# revA-voltlog-mod.net
KiCad netlist of a schematic drawn in EAGLE
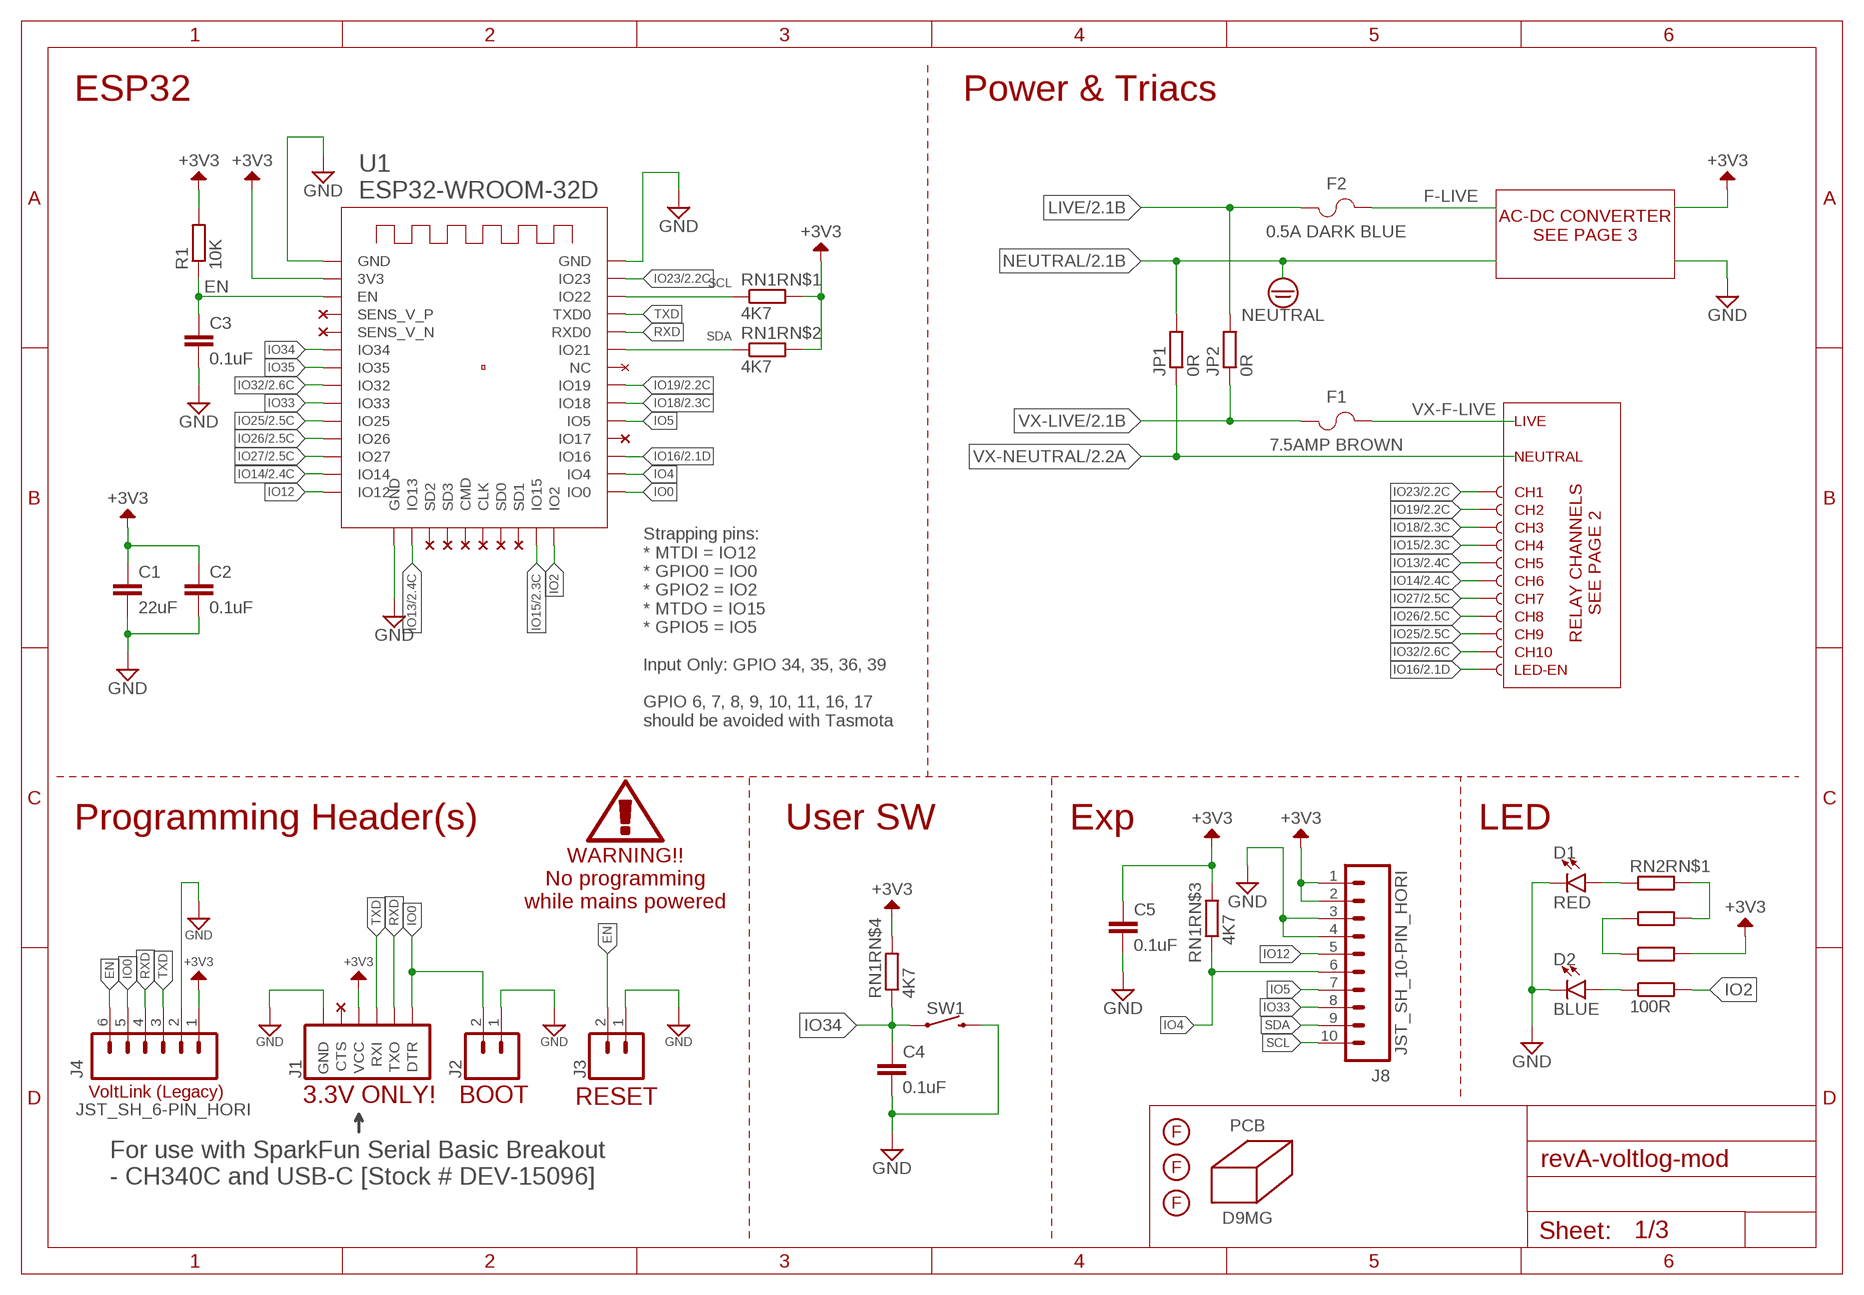
[diagram p0: schematic, sheet 1]
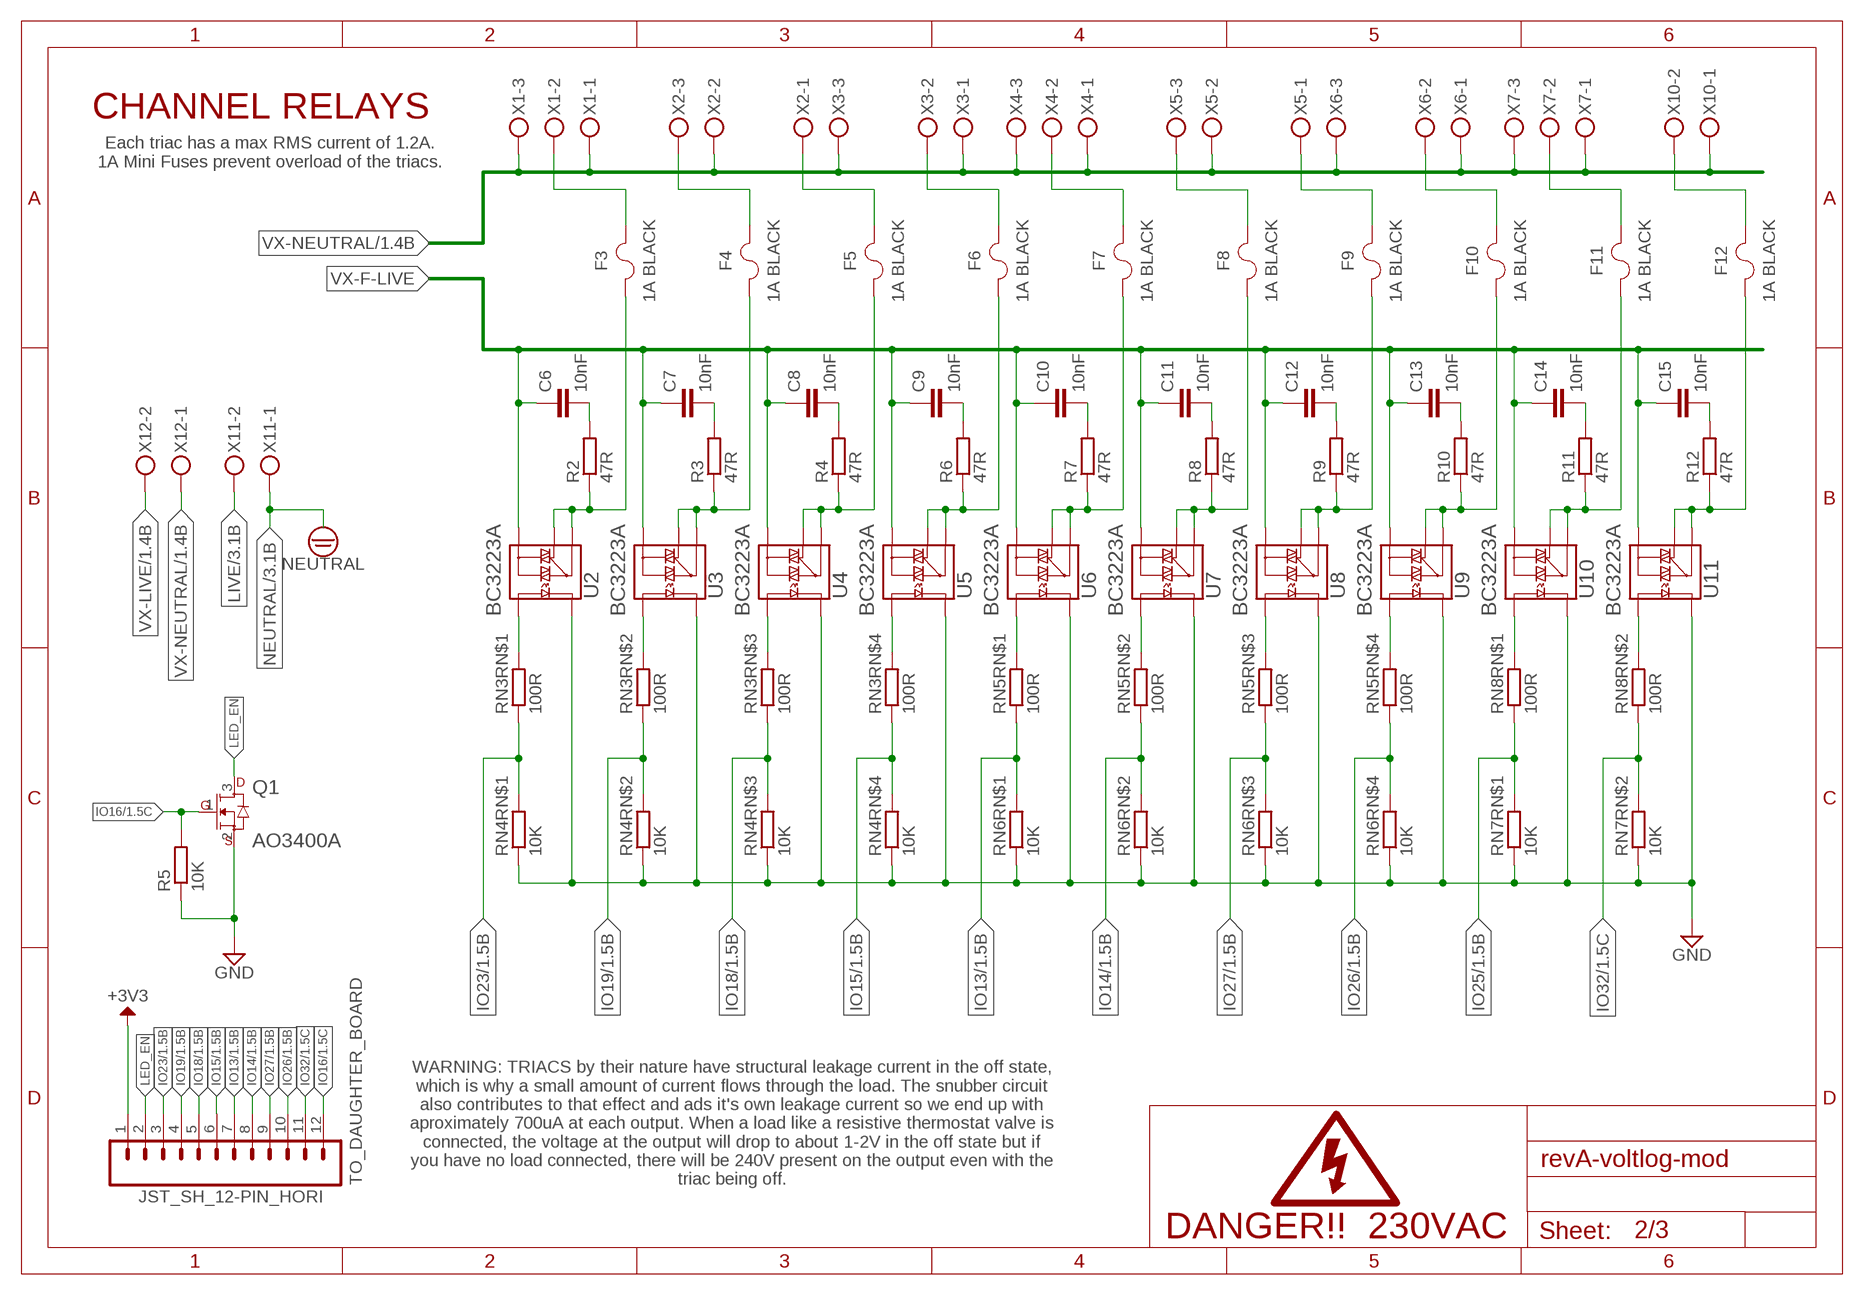
[diagram p1: schematic, sheet 2]
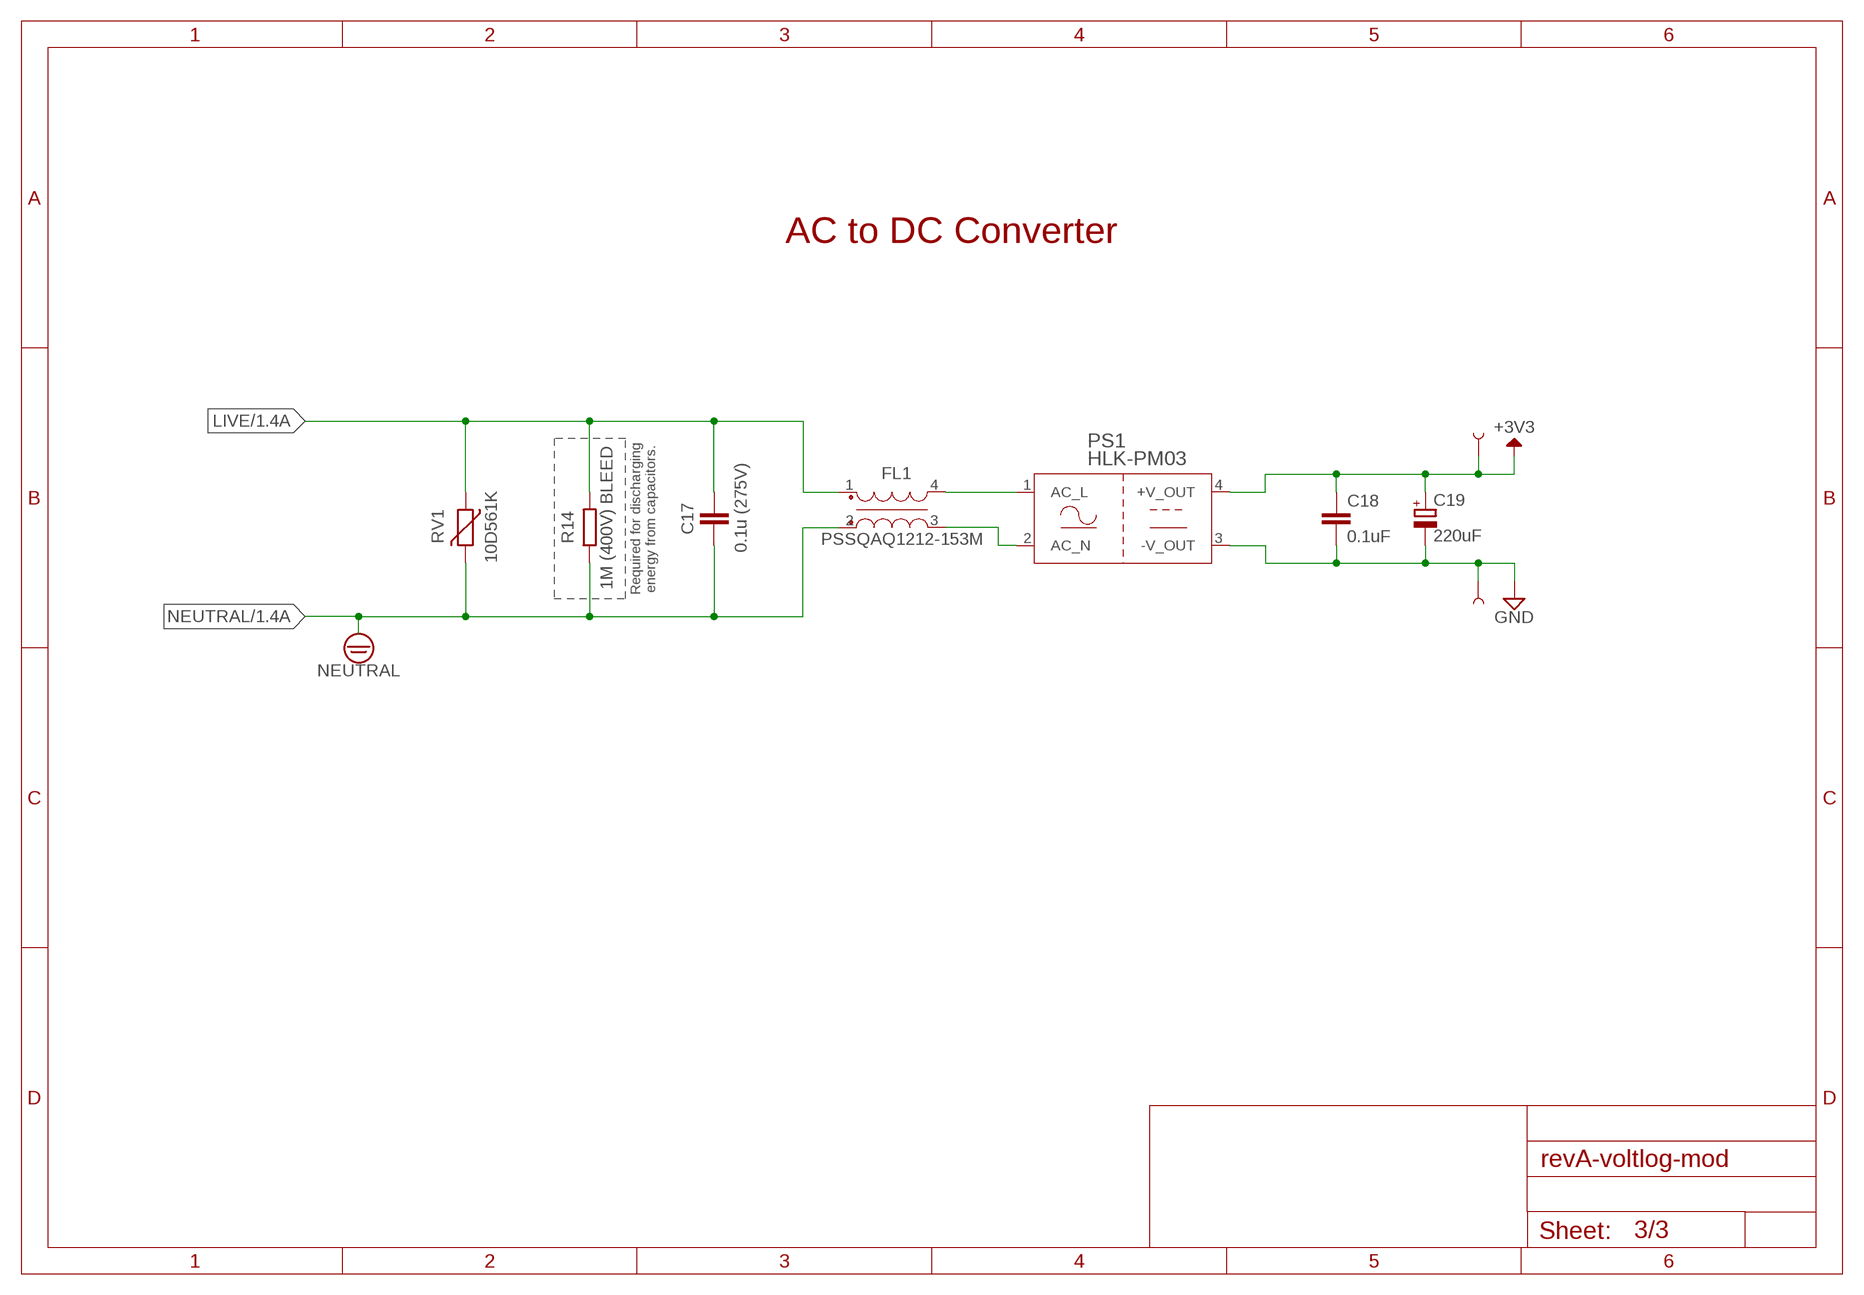
[diagram p2: schematic, sheet 3]

(export (version "E")
  (design (tool "Eeschema 10.0.6"))
  (components
    (comp (ref "C1")
      (value "22uF")
      (footprint "eagle-import:C0603")
      (libsource (lib "eagle-import") (part "C-EUC0603"))
    )
    (comp (ref "C2")
      (value "0.1uF")
      (footprint "eagle-import:C0603")
      (libsource (lib "eagle-import") (part "C-EUC0603"))
    )
    (comp (ref "C3")
      (value "0.1uF")
      (footprint "eagle-import:C0603")
      (libsource (lib "eagle-import") (part "C-EUC0603"))
    )
    (comp (ref "C4")
      (value "0.1uF")
      (footprint "eagle-import:C0603")
      (libsource (lib "eagle-import") (part "C-EUC0603"))
    )
    (comp (ref "C5")
      (value "0.1uF")
      (footprint "eagle-import:C0603")
      (libsource (lib "eagle-import") (part "C-EUC0603"))
    )
    (comp (ref "CH2")
      (value "TEST-POINT3X4")
      (footprint "eagle-import:PAD.03X.04")
      (libsource (lib "eagle-import") (part "TEST-POINT3X4"))
    )
    (comp (ref "D1")
      (value "RED")
      (footprint "eagle-import:LED-0805")
      (libsource (lib "eagle-import") (part "LED-RED-0805"))
    )
    (comp (ref "D2")
      (value "BLUE")
      (footprint "eagle-import:LED-0805")
      (libsource (lib "eagle-import") (part "LED-GREEN0805-PG"))
    )
    (comp (ref "F1")
      (value "7.5AMP BROWN")
      (footprint "eagle-import:FUSE-MINI-THI")
      (libsource (lib "eagle-import") (part "FUSEMINI-TH"))
    )
    (comp (ref "F2")
      (value "0.5A DARK BLUE")
      (footprint "eagle-import:FUSE-MINI-THI")
      (libsource (lib "eagle-import") (part "FUSEMINI-TH"))
    )
    (comp (ref "IO13")
      (value "TEST-POINT3X4")
      (footprint "eagle-import:PAD.03X.04")
      (libsource (lib "eagle-import") (part "TEST-POINT3X4"))
    )
    (comp (ref "J1")
      (value "6_PIN_SERIAL_TARGETSILK")
      (footprint "eagle-import:6_PIN_SERIAL_TARGET_SIDE_W_SILK")
      (libsource (lib "eagle-import") (part "6_PIN_SERIAL_TARGETSILK"))
    )
    (comp (ref "J2")
      (value "CONN_02")
      (footprint "eagle-import:1X02")
      (libsource (lib "eagle-import") (part "CONN_02"))
    )
    (comp (ref "J3")
      (value "CONN_02")
      (footprint "eagle-import:1X02")
      (libsource (lib "eagle-import") (part "CONN_02"))
    )
    (comp (ref "J4")
      (value "JST_SH_6-PIN_HORI")
      (footprint "eagle-import:JST-SH-6-SMD-HORI-1.0MM")
      (libsource (lib "eagle-import") (part "JST_SH_6-PIN_HORI"))
    )
    (comp (ref "J8")
      (value "JST_SH_10-PIN_HORI")
      (footprint "eagle-import:JST-SH-10-SMD-HORI-1.0MM")
      (libsource (lib "eagle-import") (part "JST_SH_10-PIN_HORI"))
    )
    (comp (ref "JP1")
      (value "0R")
      (footprint "eagle-import:R1210")
      (libsource (lib "eagle-import") (part "R-EU_R1210"))
    )
    (comp (ref "JP2")
      (value "0R")
      (footprint "eagle-import:R1210")
      (libsource (lib "eagle-import") (part "R-EU_R1210"))
    )
    (comp (ref "PCB")
      (value "D9MG")
      (footprint "eagle-import:D9MG-160X90X50")
      (libsource (lib "eagle-import") (part "D9MG"))
    )
    (comp (ref "R1")
      (value "10K")
      (footprint "eagle-import:R0603")
      (libsource (lib "eagle-import") (part "R-EU_R0603"))
    )
    (comp (ref "RN1")
      (value "4K7")
      (footprint "eagle-import:R1206X4")
      (libsource (lib "eagle-import") (part "R-EU-41206"))
    )
    (comp (ref "RN2")
      (value "100R")
      (footprint "eagle-import:R1206X4")
      (libsource (lib "eagle-import") (part "R-EU-41206"))
    )
    (comp (ref "SW1")
      (value "MOMENTARY-SWITCH-SPST-SMD-5.2-TALL-REDUNDANT")
      (footprint "eagle-import:TACTILE_SWITCH_SMD_5.2MM")
      (libsource (lib "eagle-import") (part "MOMENTARY-SWITCH-SPST-SMD-5.2-TALL-REDUNDANT"))
    )
    (comp (ref "TP1")
      (value "TEST-POINT3X4")
      (footprint "eagle-import:PAD.03X.04")
      (libsource (lib "eagle-import") (part "TEST-POINT3X4"))
    )
    (comp (ref "TP3")
      (value "TEST-POINT3X4")
      (footprint "eagle-import:PAD.03X.04")
      (libsource (lib "eagle-import") (part "TEST-POINT3X4"))
    )
    (comp (ref "TP4")
      (value "TEST-POINT3X4")
      (footprint "eagle-import:PAD.03X.04")
      (libsource (lib "eagle-import") (part "TEST-POINT3X4"))
    )
    (comp (ref "TP6")
      (value "TEST-POINT3X4")
      (footprint "eagle-import:PAD.03X.04")
      (libsource (lib "eagle-import") (part "TEST-POINT3X4"))
    )
    (comp (ref "TP7")
      (value "TEST-POINT3X4")
      (footprint "eagle-import:PAD.03X.04")
      (libsource (lib "eagle-import") (part "TEST-POINT3X4"))
    )
    (comp (ref "TP8")
      (value "TEST-POINT3X4")
      (footprint "eagle-import:PAD.03X.04")
      (libsource (lib "eagle-import") (part "TEST-POINT3X4"))
    )
    (comp (ref "TP9")
      (value "TEST-POINT3X4")
      (footprint "eagle-import:PAD.03X.04")
      (libsource (lib "eagle-import") (part "TEST-POINT3X4"))
    )
    (comp (ref "TP10")
      (value "TEST-POINT3X4")
      (footprint "eagle-import:PAD.03X.04")
      (libsource (lib "eagle-import") (part "TEST-POINT3X4"))
    )
    (comp (ref "TP11")
      (value "TEST-POINT3X4")
      (footprint "eagle-import:PAD.03X.04")
      (libsource (lib "eagle-import") (part "TEST-POINT3X4"))
    )
    (comp (ref "U$2")
      (value "FIDUCIAL")
      (footprint "eagle-import:FIDUCIAL")
      (libsource (lib "eagle-import") (part "FIDUCIAL"))
    )
    (comp (ref "U$3")
      (value "FIDUCIAL")
      (footprint "eagle-import:FIDUCIAL")
      (libsource (lib "eagle-import") (part "FIDUCIAL"))
    )
    (comp (ref "U$4")
      (value "FIDUCIAL")
      (footprint "eagle-import:FIDUCIAL")
      (libsource (lib "eagle-import") (part "FIDUCIAL"))
    )
    (comp (ref "U1")
      (value "ESP32-WROOM-32D")
      (footprint "eagle-import:ESP32-WROOM-32_EXP")
      (libsource (lib "eagle-import") (part "ESP32-WROOM-32D"))
    )
    (comp (ref "C17")
      (value "0.1u (275V)")
      (footprint "eagle-import:C075-063X106")
      (libsource (lib "eagle-import") (part "C-EU075-063X106"))
    )
    (comp (ref "C18")
      (value "0.1uF")
      (footprint "eagle-import:C1206")
      (libsource (lib "eagle-import") (part "C-EUC1206"))
    )
    (comp (ref "C19")
      (value "220uF")
      (footprint "eagle-import:UD-6,3X7,7_NICHICON")
      (libsource (lib "eagle-import") (part "CPOL-EUUD-6,3X7,7"))
    )
    (comp (ref "FL1")
      (value "PSSQAQ1212-153M")
      (footprint "eagle-import:CHOKE-SMD-20X17MM")
      (libsource (lib "eagle-import") (part "PSSQAQ1212"))
    )
    (comp (ref "PS1")
      (value "HLK-PM03")
      (footprint "eagle-import:DIP4_HLK-PM_HLK")
      (libsource (lib "eagle-import") (part "HLK-PM03"))
    )
    (comp (ref "R14")
      (value "1M (400V) BLEED")
      (footprint "eagle-import:R2010W")
      (libsource (lib "eagle-import") (part "R-EU_R2010W"))
    )
    (comp (ref "RV1")
      (value "10D561K")
      (footprint "eagle-import:R-7,5")
      (libsource (lib "eagle-import") (part "VARISTOR-7,5"))
    )
    (comp (ref "TP2")
      (value "TEST-POINT3X5")
      (footprint "eagle-import:PAD.03X.05")
      (libsource (lib "eagle-import") (part "TEST-POINT3X5"))
    )
    (comp (ref "TP5")
      (value "TEST-POINT3X5")
      (footprint "eagle-import:PAD.03X.05")
      (libsource (lib "eagle-import") (part "TEST-POINT3X5"))
    )
    (comp (ref "C6")
      (value "10nF")
      (footprint "eagle-import:C050-045X075")
      (libsource (lib "eagle-import") (part "C-EU050-045X075"))
    )
    (comp (ref "C7")
      (value "10nF")
      (footprint "eagle-import:C050-045X075")
      (libsource (lib "eagle-import") (part "C-EU050-045X075"))
    )
    (comp (ref "C8")
      (value "10nF")
      (footprint "eagle-import:C050-045X075")
      (libsource (lib "eagle-import") (part "C-EU050-045X075"))
    )
    (comp (ref "C9")
      (value "10nF")
      (footprint "eagle-import:C050-045X075")
      (libsource (lib "eagle-import") (part "C-EU050-045X075"))
    )
    (comp (ref "C10")
      (value "10nF")
      (footprint "eagle-import:C050-045X075")
      (libsource (lib "eagle-import") (part "C-EU050-045X075"))
    )
    (comp (ref "C11")
      (value "10nF")
      (footprint "eagle-import:C050-045X075")
      (libsource (lib "eagle-import") (part "C-EU050-045X075"))
    )
    (comp (ref "C12")
      (value "10nF")
      (footprint "eagle-import:C050-045X075")
      (libsource (lib "eagle-import") (part "C-EU050-045X075"))
    )
    (comp (ref "C13")
      (value "10nF")
      (footprint "eagle-import:C050-045X075")
      (libsource (lib "eagle-import") (part "C-EU050-045X075"))
    )
    (comp (ref "C14")
      (value "10nF")
      (footprint "eagle-import:C050-045X075")
      (libsource (lib "eagle-import") (part "C-EU050-045X075"))
    )
    (comp (ref "C15")
      (value "10nF")
      (footprint "eagle-import:C050-045X075")
      (libsource (lib "eagle-import") (part "C-EU050-045X075"))
    )
    (comp (ref "F3")
      (value "1A BLACK")
      (footprint "eagle-import:FUSE-MINI-THI")
      (libsource (lib "eagle-import") (part "FUSEMINI-TH"))
    )
    (comp (ref "F4")
      (value "1A BLACK")
      (footprint "eagle-import:FUSE-MINI-THI")
      (libsource (lib "eagle-import") (part "FUSEMINI-TH"))
    )
    (comp (ref "F5")
      (value "1A BLACK")
      (footprint "eagle-import:FUSE-MINI-THI")
      (libsource (lib "eagle-import") (part "FUSEMINI-TH"))
    )
    (comp (ref "F6")
      (value "1A BLACK")
      (footprint "eagle-import:FUSE-MINI-THI")
      (libsource (lib "eagle-import") (part "FUSEMINI-TH"))
    )
    (comp (ref "F7")
      (value "1A BLACK")
      (footprint "eagle-import:FUSE-MINI-THI")
      (libsource (lib "eagle-import") (part "FUSEMINI-TH"))
    )
    (comp (ref "F8")
      (value "1A BLACK")
      (footprint "eagle-import:FUSE-MINI-THI")
      (libsource (lib "eagle-import") (part "FUSEMINI-TH"))
    )
    (comp (ref "F9")
      (value "1A BLACK")
      (footprint "eagle-import:FUSE-MINI-THI")
      (libsource (lib "eagle-import") (part "FUSEMINI-TH"))
    )
    (comp (ref "F10")
      (value "1A BLACK")
      (footprint "eagle-import:FUSE-MINI-THI")
      (libsource (lib "eagle-import") (part "FUSEMINI-TH"))
    )
    (comp (ref "F11")
      (value "1A BLACK")
      (footprint "eagle-import:FUSE-MINI-THI")
      (libsource (lib "eagle-import") (part "FUSEMINI-TH"))
    )
    (comp (ref "F12")
      (value "1A BLACK")
      (footprint "eagle-import:FUSE-MINI-THI")
      (libsource (lib "eagle-import") (part "FUSEMINI-TH"))
    )
    (comp (ref "Q1")
      (value "AO3400A")
      (footprint "eagle-import:SOT-23-3L_AOS")
      (libsource (lib "eagle-import") (part "AO3400A"))
    )
    (comp (ref "R2")
      (value "47R")
      (footprint "eagle-import:R1206W")
      (libsource (lib "eagle-import") (part "R-EU_R1206W"))
    )
    (comp (ref "R3")
      (value "47R")
      (footprint "eagle-import:R1206W")
      (libsource (lib "eagle-import") (part "R-EU_R1206W"))
    )
    (comp (ref "R4")
      (value "47R")
      (footprint "eagle-import:R1206W")
      (libsource (lib "eagle-import") (part "R-EU_R1206W"))
    )
    (comp (ref "R5")
      (value "10K")
      (footprint "eagle-import:R0603")
      (libsource (lib "eagle-import") (part "R-EU_R0603"))
    )
    (comp (ref "R6")
      (value "47R")
      (footprint "eagle-import:R1206W")
      (libsource (lib "eagle-import") (part "R-EU_R1206W"))
    )
    (comp (ref "R7")
      (value "47R")
      (footprint "eagle-import:R1206W")
      (libsource (lib "eagle-import") (part "R-EU_R1206W"))
    )
    (comp (ref "R8")
      (value "47R")
      (footprint "eagle-import:R1206W")
      (libsource (lib "eagle-import") (part "R-EU_R1206W"))
    )
    (comp (ref "R9")
      (value "47R")
      (footprint "eagle-import:R1206W")
      (libsource (lib "eagle-import") (part "R-EU_R1206W"))
    )
    (comp (ref "R10")
      (value "47R")
      (footprint "eagle-import:R1206W")
      (libsource (lib "eagle-import") (part "R-EU_R1206W"))
    )
    (comp (ref "R11")
      (value "47R")
      (footprint "eagle-import:R1206W")
      (libsource (lib "eagle-import") (part "R-EU_R1206W"))
    )
    (comp (ref "R12")
      (value "47R")
      (footprint "eagle-import:R1206W")
      (libsource (lib "eagle-import") (part "R-EU_R1206W"))
    )
    (comp (ref "RN3")
      (value "100R")
      (footprint "eagle-import:R1206X4")
      (libsource (lib "eagle-import") (part "R-EU-41206"))
    )
    (comp (ref "RN4")
      (value "10K")
      (footprint "eagle-import:R1206X4")
      (libsource (lib "eagle-import") (part "R-EU-41206"))
    )
    (comp (ref "RN5")
      (value "100R")
      (footprint "eagle-import:R1206X4")
      (libsource (lib "eagle-import") (part "R-EU-41206"))
    )
    (comp (ref "RN6")
      (value "10K")
      (footprint "eagle-import:R1206X4")
      (libsource (lib "eagle-import") (part "R-EU-41206"))
    )
    (comp (ref "RN7")
      (value "10K")
      (footprint "eagle-import:R1206X4")
      (libsource (lib "eagle-import") (part "R-EU-41206"))
    )
    (comp (ref "RN8")
      (value "100R")
      (footprint "eagle-import:R1206X4")
      (libsource (lib "eagle-import") (part "R-EU-41206"))
    )
    (comp (ref "TO_DAUGHTER_BOARD")
      (value "JST_SH_12-PIN_HORI")
      (footprint "eagle-import:JST-SH-12-SMD-HORI-1.0MM")
      (libsource (lib "eagle-import") (part "JST_SH_12-PIN_HORI"))
    )
    (comp (ref "U2")
      (value "BC3223A")
      (footprint "eagle-import:7-PIN_DUAL-DIP-SMD")
      (libsource (lib "eagle-import") (part "BCX2X3A"))
    )
    (comp (ref "U3")
      (value "BC3223A")
      (footprint "eagle-import:7-PIN_DUAL-DIP-SMD")
      (libsource (lib "eagle-import") (part "BCX2X3A"))
    )
    (comp (ref "U4")
      (value "BC3223A")
      (footprint "eagle-import:7-PIN_DUAL-DIP-SMD")
      (libsource (lib "eagle-import") (part "BCX2X3A"))
    )
    (comp (ref "U5")
      (value "BC3223A")
      (footprint "eagle-import:7-PIN_DUAL-DIP-SMD")
      (libsource (lib "eagle-import") (part "BCX2X3A"))
    )
    (comp (ref "U6")
      (value "BC3223A")
      (footprint "eagle-import:7-PIN_DUAL-DIP-SMD")
      (libsource (lib "eagle-import") (part "BCX2X3A"))
    )
    (comp (ref "U7")
      (value "BC3223A")
      (footprint "eagle-import:7-PIN_DUAL-DIP-SMD")
      (libsource (lib "eagle-import") (part "BCX2X3A"))
    )
    (comp (ref "U8")
      (value "BC3223A")
      (footprint "eagle-import:7-PIN_DUAL-DIP-SMD")
      (libsource (lib "eagle-import") (part "BCX2X3A"))
    )
    (comp (ref "U9")
      (value "BC3223A")
      (footprint "eagle-import:7-PIN_DUAL-DIP-SMD")
      (libsource (lib "eagle-import") (part "BCX2X3A"))
    )
    (comp (ref "U10")
      (value "BC3223A")
      (footprint "eagle-import:7-PIN_DUAL-DIP-SMD")
      (libsource (lib "eagle-import") (part "BCX2X3A"))
    )
    (comp (ref "U11")
      (value "BC3223A")
      (footprint "eagle-import:7-PIN_DUAL-DIP-SMD")
      (libsource (lib "eagle-import") (part "BCX2X3A"))
    )
    (comp (ref "X1")
      (value "MKDSN1,5/3-5,08")
      (footprint "eagle-import:MKDSN1,5_3-5,08")
      (libsource (lib "eagle-import") (part "MKDSN1,5/3-5,08"))
    )
    (comp (ref "X2")
      (value "MKDSN1,5/3-5,08")
      (footprint "eagle-import:MKDSN1,5_3-5,08")
      (libsource (lib "eagle-import") (part "MKDSN1,5/3-5,08"))
    )
    (comp (ref "X3")
      (value "MKDSN1,5/3-5,08")
      (footprint "eagle-import:MKDSN1,5_3-5,08")
      (libsource (lib "eagle-import") (part "MKDSN1,5/3-5,08"))
    )
    (comp (ref "X4")
      (value "MKDSN1,5/3-5,08")
      (footprint "eagle-import:MKDSN1,5_3-5,08")
      (libsource (lib "eagle-import") (part "MKDSN1,5/3-5,08"))
    )
    (comp (ref "X5")
      (value "MKDSN1,5/3-5,08")
      (footprint "eagle-import:MKDSN1,5_3-5,08")
      (libsource (lib "eagle-import") (part "MKDSN1,5/3-5,08"))
    )
    (comp (ref "X6")
      (value "MKDSN1,5/3-5,08")
      (footprint "eagle-import:MKDSN1,5_3-5,08")
      (libsource (lib "eagle-import") (part "MKDSN1,5/3-5,08"))
    )
    (comp (ref "X7")
      (value "MKDSN1,5/3-5,08")
      (footprint "eagle-import:MKDSN1,5_3-5,08")
      (libsource (lib "eagle-import") (part "MKDSN1,5/3-5,08"))
    )
    (comp (ref "X10")
      (value "MKDSN1,5/2-5,08")
      (footprint "eagle-import:MKDSN1,5_2-5,08")
      (libsource (lib "eagle-import") (part "MKDSN1,5/2-5,08"))
    )
    (comp (ref "X11")
      (value "MKDSN1,5/2-5,08")
      (footprint "eagle-import:MKDSN1,5_2-5,08")
      (libsource (lib "eagle-import") (part "MKDSN1,5/2-5,08"))
    )
    (comp (ref "X12")
      (value "MKDSN1,5/2-5,08")
      (footprint "eagle-import:MKDSN1,5_2-5,08")
      (libsource (lib "eagle-import") (part "MKDSN1,5/2-5,08"))
    )
  )
  (nets
    (net (code "1") (name "+3V3") (class "Default")
      (node (ref "C1") (pin "1") (pinfunction "1_1") (pintype "passive"))
      (node (ref "C18") (pin "1") (pinfunction "1_1") (pintype "passive"))
      (node (ref "C19") (pin "+") (pinfunction "+_+") (pintype "passive"))
      (node (ref "C2") (pin "1") (pinfunction "1_1") (pintype "passive"))
      (node (ref "C5") (pin "1") (pinfunction "1_1") (pintype "passive"))
      (node (ref "J1") (pin "4") (pinfunction "VCC_4") (pintype "passive"))
      (node (ref "J4") (pin "1") (pinfunction "1_1") (pintype "passive"))
      (node (ref "J8") (pin "1") (pinfunction "1_1") (pintype "passive"))
      (node (ref "J8") (pin "2") (pinfunction "2_2") (pintype "passive"))
      (node (ref "PS1") (pin "4") (pinfunction "+V_OUT_4") (pintype "power_in"))
      (node (ref "R1") (pin "2") (pinfunction "2_2") (pintype "passive"))
      (node (ref "RN1") (pin "5") (pinfunction "2_5") (pintype "passive"))
      (node (ref "RN1") (pin "6") (pinfunction "2_6") (pintype "passive"))
      (node (ref "RN1") (pin "7") (pinfunction "2_7") (pintype "passive"))
      (node (ref "RN1") (pin "8") (pinfunction "2_8") (pintype "passive"))
      (node (ref "RN2") (pin "6") (pinfunction "2_6") (pintype "passive"))
      (node (ref "TO_DAUGHTER_BOARD") (pin "1") (pinfunction "1_1") (pintype "passive"))
      (node (ref "TP2") (pin "1") (pinfunction "1_1") (pintype "bidirectional"))
      (node (ref "U1") (pin "2") (pinfunction "3V3_2") (pintype "passive"))
    )
    (net (code "2") (name "EN") (class "Default")
      (node (ref "C3") (pin "1") (pinfunction "1_1") (pintype "passive"))
      (node (ref "J3") (pin "2") (pinfunction "2_2") (pintype "passive"))
      (node (ref "J4") (pin "6") (pinfunction "6_6") (pintype "passive"))
      (node (ref "R1") (pin "1") (pinfunction "1_1") (pintype "passive"))
      (node (ref "U1") (pin "3") (pinfunction "EN_3") (pintype "passive"))
    )
    (net (code "3") (name "F-LIVE") (class "Default")
      (node (ref "F2") (pin "2@1") (pinfunction "P$2_2@1") (pintype "bidirectional"))
      (node (ref "F2") (pin "2@2") (pinfunction "P$2_2@2") (pintype "bidirectional"))
    )
    (net (code "4") (name "GND") (class "Default")
      (node (ref "C1") (pin "2") (pinfunction "2_2") (pintype "passive"))
      (node (ref "C18") (pin "2") (pinfunction "2_2") (pintype "passive"))
      (node (ref "C19") (pin "-") (pinfunction "-_-") (pintype "passive"))
      (node (ref "C2") (pin "2") (pinfunction "2_2") (pintype "passive"))
      (node (ref "C3") (pin "2") (pinfunction "2_2") (pintype "passive"))
      (node (ref "C4") (pin "2") (pinfunction "2_2") (pintype "passive"))
      (node (ref "C5") (pin "2") (pinfunction "2_2") (pintype "passive"))
      (node (ref "D1") (pin "C") (pinfunction "C_C") (pintype "passive"))
      (node (ref "D2") (pin "C") (pinfunction "C_C") (pintype "passive"))
      (node (ref "J1") (pin "6") (pinfunction "GND_6") (pintype "passive"))
      (node (ref "J2") (pin "1") (pinfunction "1_1") (pintype "passive"))
      (node (ref "J3") (pin "1") (pinfunction "1_1") (pintype "passive"))
      (node (ref "J4") (pin "2") (pinfunction "2_2") (pintype "passive"))
      (node (ref "J8") (pin "3") (pinfunction "3_3") (pintype "passive"))
      (node (ref "J8") (pin "4") (pinfunction "4_4") (pintype "passive"))
      (node (ref "PS1") (pin "3") (pinfunction "-V_OUT_3") (pintype "power_in"))
      (node (ref "Q1") (pin "2") (pinfunction "S_2") (pintype "passive"))
      (node (ref "R5") (pin "1") (pinfunction "1_1") (pintype "passive"))
      (node (ref "RN4") (pin "1") (pinfunction "1_1") (pintype "passive"))
      (node (ref "RN4") (pin "2") (pinfunction "1_2") (pintype "passive"))
      (node (ref "RN4") (pin "3") (pinfunction "1_3") (pintype "passive"))
      (node (ref "RN4") (pin "4") (pinfunction "1_4") (pintype "passive"))
      (node (ref "RN6") (pin "1") (pinfunction "1_1") (pintype "passive"))
      (node (ref "RN6") (pin "2") (pinfunction "1_2") (pintype "passive"))
      (node (ref "RN6") (pin "3") (pinfunction "1_3") (pintype "passive"))
      (node (ref "RN6") (pin "4") (pinfunction "1_4") (pintype "passive"))
      (node (ref "RN7") (pin "1") (pinfunction "1_1") (pintype "passive"))
      (node (ref "RN7") (pin "2") (pinfunction "1_2") (pintype "passive"))
      (node (ref "SW1") (pin "3") (pinfunction "2_3") (pintype "passive"))
      (node (ref "SW1") (pin "4") (pinfunction "2_4") (pintype "passive"))
      (node (ref "TP5") (pin "1") (pinfunction "1_1") (pintype "bidirectional"))
      (node (ref "U1") (pin "1") (pinfunction "GND_1") (pintype "passive"))
      (node (ref "U1") (pin "15") (pinfunction "GND_15") (pintype "passive"))
      (node (ref "U1") (pin "38") (pinfunction "GND_38") (pintype "passive"))
      (node (ref "U1") (pin "39@1") (pinfunction "GND_39@1") (pintype "passive"))
      (node (ref "U1") (pin "39@2") (pinfunction "GND_39@2") (pintype "passive"))
      (node (ref "U1") (pin "39@3") (pinfunction "GND_39@3") (pintype "passive"))
      (node (ref "U1") (pin "39@4") (pinfunction "GND_39@4") (pintype "passive"))
      (node (ref "U1") (pin "39@5") (pinfunction "GND_39@5") (pintype "passive"))
      (node (ref "U1") (pin "39@6") (pinfunction "GND_39@6") (pintype "passive"))
      (node (ref "U1") (pin "39@7") (pinfunction "GND_39@7") (pintype "passive"))
      (node (ref "U1") (pin "39@8") (pinfunction "GND_39@8") (pintype "passive"))
      (node (ref "U1") (pin "39@9") (pinfunction "GND_39@9") (pintype "passive"))
      (node (ref "U10") (pin "1@1") (pinfunction "C_1@1") (pintype "bidirectional"))
      (node (ref "U10") (pin "1@2") (pinfunction "C_1@2") (pintype "bidirectional"))
      (node (ref "U10") (pin "3@1") (pinfunction "C_3@1") (pintype "bidirectional"))
      (node (ref "U10") (pin "3@2") (pinfunction "C_3@2") (pintype "bidirectional"))
      (node (ref "U10") (pin "4@1") (pinfunction "C_4@1") (pintype "bidirectional"))
      (node (ref "U10") (pin "4@2") (pinfunction "C_4@2") (pintype "bidirectional"))
      (node (ref "U11") (pin "1@1") (pinfunction "C_1@1") (pintype "bidirectional"))
      (node (ref "U11") (pin "1@2") (pinfunction "C_1@2") (pintype "bidirectional"))
      (node (ref "U11") (pin "3@1") (pinfunction "C_3@1") (pintype "bidirectional"))
      (node (ref "U11") (pin "3@2") (pinfunction "C_3@2") (pintype "bidirectional"))
      (node (ref "U11") (pin "4@1") (pinfunction "C_4@1") (pintype "bidirectional"))
      (node (ref "U11") (pin "4@2") (pinfunction "C_4@2") (pintype "bidirectional"))
      (node (ref "U2") (pin "1@1") (pinfunction "C_1@1") (pintype "bidirectional"))
      (node (ref "U2") (pin "1@2") (pinfunction "C_1@2") (pintype "bidirectional"))
      (node (ref "U2") (pin "3@1") (pinfunction "C_3@1") (pintype "bidirectional"))
      (node (ref "U2") (pin "3@2") (pinfunction "C_3@2") (pintype "bidirectional"))
      (node (ref "U2") (pin "4@1") (pinfunction "C_4@1") (pintype "bidirectional"))
      (node (ref "U2") (pin "4@2") (pinfunction "C_4@2") (pintype "bidirectional"))
      (node (ref "U3") (pin "1@1") (pinfunction "C_1@1") (pintype "bidirectional"))
      (node (ref "U3") (pin "1@2") (pinfunction "C_1@2") (pintype "bidirectional"))
      (node (ref "U3") (pin "3@1") (pinfunction "C_3@1") (pintype "bidirectional"))
      (node (ref "U3") (pin "3@2") (pinfunction "C_3@2") (pintype "bidirectional"))
      (node (ref "U3") (pin "4@1") (pinfunction "C_4@1") (pintype "bidirectional"))
      (node (ref "U3") (pin "4@2") (pinfunction "C_4@2") (pintype "bidirectional"))
      (node (ref "U4") (pin "1@1") (pinfunction "C_1@1") (pintype "bidirectional"))
      (node (ref "U4") (pin "1@2") (pinfunction "C_1@2") (pintype "bidirectional"))
      (node (ref "U4") (pin "3@1") (pinfunction "C_3@1") (pintype "bidirectional"))
      (node (ref "U4") (pin "3@2") (pinfunction "C_3@2") (pintype "bidirectional"))
      (node (ref "U4") (pin "4@1") (pinfunction "C_4@1") (pintype "bidirectional"))
      (node (ref "U4") (pin "4@2") (pinfunction "C_4@2") (pintype "bidirectional"))
      (node (ref "U5") (pin "1@1") (pinfunction "C_1@1") (pintype "bidirectional"))
      (node (ref "U5") (pin "1@2") (pinfunction "C_1@2") (pintype "bidirectional"))
      (node (ref "U5") (pin "3@1") (pinfunction "C_3@1") (pintype "bidirectional"))
      (node (ref "U5") (pin "3@2") (pinfunction "C_3@2") (pintype "bidirectional"))
      (node (ref "U5") (pin "4@1") (pinfunction "C_4@1") (pintype "bidirectional"))
      (node (ref "U5") (pin "4@2") (pinfunction "C_4@2") (pintype "bidirectional"))
      (node (ref "U6") (pin "1@1") (pinfunction "C_1@1") (pintype "bidirectional"))
      (node (ref "U6") (pin "1@2") (pinfunction "C_1@2") (pintype "bidirectional"))
      (node (ref "U6") (pin "3@1") (pinfunction "C_3@1") (pintype "bidirectional"))
      (node (ref "U6") (pin "3@2") (pinfunction "C_3@2") (pintype "bidirectional"))
      (node (ref "U6") (pin "4@1") (pinfunction "C_4@1") (pintype "bidirectional"))
      (node (ref "U6") (pin "4@2") (pinfunction "C_4@2") (pintype "bidirectional"))
      (node (ref "U7") (pin "1@1") (pinfunction "C_1@1") (pintype "bidirectional"))
      (node (ref "U7") (pin "1@2") (pinfunction "C_1@2") (pintype "bidirectional"))
      (node (ref "U7") (pin "3@1") (pinfunction "C_3@1") (pintype "bidirectional"))
      (node (ref "U7") (pin "3@2") (pinfunction "C_3@2") (pintype "bidirectional"))
      (node (ref "U7") (pin "4@1") (pinfunction "C_4@1") (pintype "bidirectional"))
      (node (ref "U7") (pin "4@2") (pinfunction "C_4@2") (pintype "bidirectional"))
      (node (ref "U8") (pin "1@1") (pinfunction "C_1@1") (pintype "bidirectional"))
      (node (ref "U8") (pin "1@2") (pinfunction "C_1@2") (pintype "bidirectional"))
      (node (ref "U8") (pin "3@1") (pinfunction "C_3@1") (pintype "bidirectional"))
      (node (ref "U8") (pin "3@2") (pinfunction "C_3@2") (pintype "bidirectional"))
      (node (ref "U8") (pin "4@1") (pinfunction "C_4@1") (pintype "bidirectional"))
      (node (ref "U8") (pin "4@2") (pinfunction "C_4@2") (pintype "bidirectional"))
      (node (ref "U9") (pin "1@1") (pinfunction "C_1@1") (pintype "bidirectional"))
      (node (ref "U9") (pin "1@2") (pinfunction "C_1@2") (pintype "bidirectional"))
      (node (ref "U9") (pin "3@1") (pinfunction "C_3@1") (pintype "bidirectional"))
      (node (ref "U9") (pin "3@2") (pinfunction "C_3@2") (pintype "bidirectional"))
      (node (ref "U9") (pin "4@1") (pinfunction "C_4@1") (pintype "bidirectional"))
      (node (ref "U9") (pin "4@2") (pinfunction "C_4@2") (pintype "bidirectional"))
    )
    (net (code "5") (name "IO0") (class "Default")
      (node (ref "J1") (pin "1") (pinfunction "DTR_1") (pintype "passive"))
      (node (ref "J2") (pin "2") (pinfunction "2_2") (pintype "passive"))
      (node (ref "J4") (pin "5") (pinfunction "5_5") (pintype "passive"))
      (node (ref "U1") (pin "25") (pinfunction "IO0_25") (pintype "passive"))
    )
    (net (code "6") (name "IO2") (class "Default")
      (node (ref "RN2") (pin "5") (pinfunction "2_5") (pintype "passive"))
      (node (ref "U1") (pin "24") (pinfunction "IO2_24") (pintype "passive"))
    )
    (net (code "7") (name "IO4") (class "Default")
      (node (ref "J8") (pin "6") (pinfunction "6_6") (pintype "passive"))
      (node (ref "RN1") (pin "3") (pinfunction "1_3") (pintype "passive"))
      (node (ref "U1") (pin "26") (pinfunction "IO4_26") (pintype "passive"))
    )
    (net (code "8") (name "IO5") (class "Default")
      (node (ref "J8") (pin "7") (pinfunction "7_7") (pintype "passive"))
      (node (ref "U1") (pin "29") (pinfunction "IO5_29") (pintype "passive"))
    )
    (net (code "9") (name "IO12") (class "Default")
      (node (ref "J8") (pin "5") (pinfunction "5_5") (pintype "passive"))
      (node (ref "U1") (pin "14") (pinfunction "IO12_14") (pintype "passive"))
    )
    (net (code "10") (name "IO13") (class "Default")
      (node (ref "IO13") (pin "1") (pinfunction "1_1") (pintype "bidirectional"))
      (node (ref "RN5") (pin "1") (pinfunction "1_1") (pintype "passive"))
      (node (ref "RN6") (pin "8") (pinfunction "2_8") (pintype "passive"))
      (node (ref "TO_DAUGHTER_BOARD") (pin "7") (pinfunction "7_7") (pintype "passive"))
      (node (ref "U1") (pin "16") (pinfunction "IO13_16") (pintype "passive"))
    )
    (net (code "11") (name "IO14") (class "Default")
      (node (ref "RN5") (pin "2") (pinfunction "1_2") (pintype "passive"))
      (node (ref "RN6") (pin "7") (pinfunction "2_7") (pintype "passive"))
      (node (ref "TO_DAUGHTER_BOARD") (pin "8") (pinfunction "8_8") (pintype "passive"))
      (node (ref "TP6") (pin "1") (pinfunction "1_1") (pintype "bidirectional"))
      (node (ref "U1") (pin "13") (pinfunction "IO14_13") (pintype "passive"))
    )
    (net (code "12") (name "IO15") (class "Default")
      (node (ref "RN3") (pin "4") (pinfunction "1_4") (pintype "passive"))
      (node (ref "RN4") (pin "5") (pinfunction "2_5") (pintype "passive"))
      (node (ref "TO_DAUGHTER_BOARD") (pin "6") (pinfunction "6_6") (pintype "passive"))
      (node (ref "TP4") (pin "1") (pinfunction "1_1") (pintype "bidirectional"))
      (node (ref "U1") (pin "23") (pinfunction "IO15_23") (pintype "passive"))
    )
    (net (code "13") (name "IO16") (class "Default")
      (node (ref "Q1") (pin "1") (pinfunction "G_1") (pintype "passive"))
      (node (ref "R5") (pin "2") (pinfunction "2_2") (pintype "passive"))
      (node (ref "TO_DAUGHTER_BOARD") (pin "12") (pinfunction "12_12") (pintype "passive"))
      (node (ref "TP11") (pin "1") (pinfunction "1_1") (pintype "bidirectional"))
      (node (ref "U1") (pin "27") (pinfunction "IO16_27") (pintype "passive"))
    )
    (net (code "14") (name "IO18") (class "Default")
      (node (ref "RN3") (pin "3") (pinfunction "1_3") (pintype "passive"))
      (node (ref "RN4") (pin "6") (pinfunction "2_6") (pintype "passive"))
      (node (ref "TO_DAUGHTER_BOARD") (pin "5") (pinfunction "5_5") (pintype "passive"))
      (node (ref "TP3") (pin "1") (pinfunction "1_1") (pintype "bidirectional"))
      (node (ref "U1") (pin "30") (pinfunction "IO18_30") (pintype "passive"))
    )
    (net (code "15") (name "IO19") (class "Default")
      (node (ref "CH2") (pin "1") (pinfunction "1_1") (pintype "bidirectional"))
      (node (ref "RN3") (pin "2") (pinfunction "1_2") (pintype "passive"))
      (node (ref "RN4") (pin "7") (pinfunction "2_7") (pintype "passive"))
      (node (ref "TO_DAUGHTER_BOARD") (pin "4") (pinfunction "4_4") (pintype "passive"))
      (node (ref "U1") (pin "31") (pinfunction "IO19_31") (pintype "passive"))
    )
    (net (code "16") (name "IO23") (class "Default")
      (node (ref "RN3") (pin "1") (pinfunction "1_1") (pintype "passive"))
      (node (ref "RN4") (pin "8") (pinfunction "2_8") (pintype "passive"))
      (node (ref "TO_DAUGHTER_BOARD") (pin "3") (pinfunction "3_3") (pintype "passive"))
      (node (ref "TP1") (pin "1") (pinfunction "1_1") (pintype "bidirectional"))
      (node (ref "U1") (pin "37") (pinfunction "IO23_37") (pintype "passive"))
    )
    (net (code "17") (name "IO25") (class "Default")
      (node (ref "RN7") (pin "8") (pinfunction "2_8") (pintype "passive"))
      (node (ref "RN8") (pin "1") (pinfunction "1_1") (pintype "passive"))
      (node (ref "TP9") (pin "1") (pinfunction "1_1") (pintype "bidirectional"))
      (node (ref "U1") (pin "10") (pinfunction "IO25_10") (pintype "passive"))
    )
    (net (code "18") (name "IO26") (class "Default")
      (node (ref "RN5") (pin "4") (pinfunction "1_4") (pintype "passive"))
      (node (ref "RN6") (pin "5") (pinfunction "2_5") (pintype "passive"))
      (node (ref "TO_DAUGHTER_BOARD") (pin "10") (pinfunction "10_10") (pintype "passive"))
      (node (ref "TP8") (pin "1") (pinfunction "1_1") (pintype "bidirectional"))
      (node (ref "U1") (pin "11") (pinfunction "IO26_11") (pintype "passive"))
    )
    (net (code "19") (name "IO27") (class "Default")
      (node (ref "RN5") (pin "3") (pinfunction "1_3") (pintype "passive"))
      (node (ref "RN6") (pin "6") (pinfunction "2_6") (pintype "passive"))
      (node (ref "TO_DAUGHTER_BOARD") (pin "9") (pinfunction "9_9") (pintype "passive"))
      (node (ref "TP7") (pin "1") (pinfunction "1_1") (pintype "bidirectional"))
      (node (ref "U1") (pin "12") (pinfunction "IO27_12") (pintype "passive"))
    )
    (net (code "20") (name "IO32") (class "Default")
      (node (ref "RN7") (pin "7") (pinfunction "2_7") (pintype "passive"))
      (node (ref "RN8") (pin "2") (pinfunction "1_2") (pintype "passive"))
      (node (ref "TO_DAUGHTER_BOARD") (pin "11") (pinfunction "11_11") (pintype "passive"))
      (node (ref "TP10") (pin "1") (pinfunction "1_1") (pintype "bidirectional"))
      (node (ref "U1") (pin "8") (pinfunction "IO32_8") (pintype "passive"))
    )
    (net (code "21") (name "IO33") (class "Default")
      (node (ref "J8") (pin "8") (pinfunction "8_8") (pintype "passive"))
      (node (ref "U1") (pin "9") (pinfunction "IO33_9") (pintype "passive"))
    )
    (net (code "22") (name "IO34") (class "Default")
      (node (ref "C4") (pin "1") (pinfunction "1_1") (pintype "passive"))
      (node (ref "RN1") (pin "4") (pinfunction "1_4") (pintype "passive"))
      (node (ref "SW1") (pin "1") (pinfunction "1_1") (pintype "passive"))
      (node (ref "SW1") (pin "2") (pinfunction "1_2") (pintype "passive"))
      (node (ref "U1") (pin "6") (pinfunction "IO34_6") (pintype "passive"))
    )
    (net (code "23") (name "IO35") (class "Default")
      (node (ref "U1") (pin "7") (pinfunction "IO35_7") (pintype "passive"))
    )
    (net (code "24") (name "LED_EN") (class "Default")
      (node (ref "Q1") (pin "3") (pinfunction "D_3") (pintype "passive"))
      (node (ref "TO_DAUGHTER_BOARD") (pin "2") (pinfunction "2_2") (pintype "passive"))
    )
    (net (code "25") (name "LIVE") (class "Default")
      (node (ref "C17") (pin "2") (pinfunction "2_2") (pintype "passive"))
      (node (ref "F2") (pin "1@1") (pinfunction "P$1_1@1") (pintype "bidirectional"))
      (node (ref "F2") (pin "1@2") (pinfunction "P$1_1@2") (pintype "bidirectional"))
      (node (ref "FL1") (pin "1") (pinfunction "1_1") (pintype "passive"))
      (node (ref "JP2") (pin "2") (pinfunction "2_2") (pintype "passive"))
      (node (ref "R14") (pin "2") (pinfunction "2_2") (pintype "passive"))
      (node (ref "RV1") (pin "1") (pinfunction "1_1") (pintype "passive"))
      (node (ref "X11") (pin "2") (pinfunction "KL_2") (pintype "passive"))
    )
    (net (code "26") (name "NEUTRAL") (class "Default")
      (node (ref "C17") (pin "1") (pinfunction "1_1") (pintype "passive"))
      (node (ref "FL1") (pin "2") (pinfunction "2_2") (pintype "passive"))
      (node (ref "JP1") (pin "2") (pinfunction "2_2") (pintype "passive"))
      (node (ref "R14") (pin "1") (pinfunction "1_1") (pintype "passive"))
      (node (ref "RV1") (pin "2") (pinfunction "2_2") (pintype "passive"))
      (node (ref "X11") (pin "1") (pinfunction "KL_1") (pintype "passive"))
    )
    (net (code "27") (name "Net-(C6-Pad2)") (class "Default")
      (node (ref "C6") (pin "2") (pinfunction "2_2") (pintype "passive"))
      (node (ref "R2") (pin "2") (pinfunction "2_2") (pintype "passive"))
    )
    (net (code "28") (name "Net-(C7-Pad2)") (class "Default")
      (node (ref "C7") (pin "2") (pinfunction "2_2") (pintype "passive"))
      (node (ref "R3") (pin "2") (pinfunction "2_2") (pintype "passive"))
    )
    (net (code "29") (name "Net-(C8-Pad2)") (class "Default")
      (node (ref "C8") (pin "2") (pinfunction "2_2") (pintype "passive"))
      (node (ref "R4") (pin "2") (pinfunction "2_2") (pintype "passive"))
    )
    (net (code "30") (name "Net-(C9-Pad2)") (class "Default")
      (node (ref "C9") (pin "2") (pinfunction "2_2") (pintype "passive"))
      (node (ref "R6") (pin "2") (pinfunction "2_2") (pintype "passive"))
    )
    (net (code "31") (name "Net-(C10-Pad2)") (class "Default")
      (node (ref "C10") (pin "2") (pinfunction "2_2") (pintype "passive"))
      (node (ref "R7") (pin "2") (pinfunction "2_2") (pintype "passive"))
    )
    (net (code "32") (name "Net-(C11-Pad2)") (class "Default")
      (node (ref "C11") (pin "2") (pinfunction "2_2") (pintype "passive"))
      (node (ref "R8") (pin "2") (pinfunction "2_2") (pintype "passive"))
    )
    (net (code "33") (name "Net-(C12-Pad2)") (class "Default")
      (node (ref "C12") (pin "2") (pinfunction "2_2") (pintype "passive"))
      (node (ref "R9") (pin "2") (pinfunction "2_2") (pintype "passive"))
    )
    (net (code "34") (name "Net-(C13-Pad2)") (class "Default")
      (node (ref "C13") (pin "2") (pinfunction "2_2") (pintype "passive"))
      (node (ref "R10") (pin "2") (pinfunction "2_2") (pintype "passive"))
    )
    (net (code "35") (name "Net-(C14-Pad2)") (class "Default")
      (node (ref "C14") (pin "2") (pinfunction "2_2") (pintype "passive"))
      (node (ref "R11") (pin "2") (pinfunction "2_2") (pintype "passive"))
    )
    (net (code "36") (name "Net-(C15-Pad2)") (class "Default")
      (node (ref "C15") (pin "2") (pinfunction "2_2") (pintype "passive"))
      (node (ref "R12") (pin "2") (pinfunction "2_2") (pintype "passive"))
    )
    (net (code "37") (name "Net-(D1-PadA)") (class "Default")
      (node (ref "D1") (pin "A") (pinfunction "A_A") (pintype "passive"))
      (node (ref "RN2") (pin "1") (pinfunction "1_1") (pintype "passive"))
    )
    (net (code "38") (name "Net-(F3-P$1-Pad1@1)") (class "Default")
      (node (ref "F3") (pin "1@1") (pinfunction "P$1_1@1") (pintype "bidirectional"))
      (node (ref "F3") (pin "1@2") (pinfunction "P$1_1@2") (pintype "bidirectional"))
      (node (ref "R2") (pin "1") (pinfunction "1_1") (pintype "passive"))
      (node (ref "U2") (pin "5@1") (pinfunction "L3_5@1") (pintype "bidirectional"))
      (node (ref "U2") (pin "5@2") (pinfunction "L3_5@2") (pintype "bidirectional"))
      (node (ref "U2") (pin "6@1") (pinfunction "L2_6@1") (pintype "bidirectional"))
      (node (ref "U2") (pin "6@2") (pinfunction "L2_6@2") (pintype "bidirectional"))
    )
    (net (code "39") (name "Net-(F4-P$1-Pad1@1)") (class "Default")
      (node (ref "F4") (pin "1@1") (pinfunction "P$1_1@1") (pintype "bidirectional"))
      (node (ref "F4") (pin "1@2") (pinfunction "P$1_1@2") (pintype "bidirectional"))
      (node (ref "R3") (pin "1") (pinfunction "1_1") (pintype "passive"))
      (node (ref "U3") (pin "5@1") (pinfunction "L3_5@1") (pintype "bidirectional"))
      (node (ref "U3") (pin "5@2") (pinfunction "L3_5@2") (pintype "bidirectional"))
      (node (ref "U3") (pin "6@1") (pinfunction "L2_6@1") (pintype "bidirectional"))
      (node (ref "U3") (pin "6@2") (pinfunction "L2_6@2") (pintype "bidirectional"))
    )
    (net (code "40") (name "Net-(F5-P$1-Pad1@1)") (class "Default")
      (node (ref "F5") (pin "1@1") (pinfunction "P$1_1@1") (pintype "bidirectional"))
      (node (ref "F5") (pin "1@2") (pinfunction "P$1_1@2") (pintype "bidirectional"))
      (node (ref "R4") (pin "1") (pinfunction "1_1") (pintype "passive"))
      (node (ref "U4") (pin "5@1") (pinfunction "L3_5@1") (pintype "bidirectional"))
      (node (ref "U4") (pin "5@2") (pinfunction "L3_5@2") (pintype "bidirectional"))
      (node (ref "U4") (pin "6@1") (pinfunction "L2_6@1") (pintype "bidirectional"))
      (node (ref "U4") (pin "6@2") (pinfunction "L2_6@2") (pintype "bidirectional"))
    )
    (net (code "41") (name "Net-(F6-P$1-Pad1@1)") (class "Default")
      (node (ref "F6") (pin "1@1") (pinfunction "P$1_1@1") (pintype "bidirectional"))
      (node (ref "F6") (pin "1@2") (pinfunction "P$1_1@2") (pintype "bidirectional"))
      (node (ref "R6") (pin "1") (pinfunction "1_1") (pintype "passive"))
      (node (ref "U5") (pin "5@1") (pinfunction "L3_5@1") (pintype "bidirectional"))
      (node (ref "U5") (pin "5@2") (pinfunction "L3_5@2") (pintype "bidirectional"))
      (node (ref "U5") (pin "6@1") (pinfunction "L2_6@1") (pintype "bidirectional"))
      (node (ref "U5") (pin "6@2") (pinfunction "L2_6@2") (pintype "bidirectional"))
    )
    (net (code "42") (name "Net-(F7-P$1-Pad1@1)") (class "Default")
      (node (ref "F7") (pin "1@1") (pinfunction "P$1_1@1") (pintype "bidirectional"))
      (node (ref "F7") (pin "1@2") (pinfunction "P$1_1@2") (pintype "bidirectional"))
      (node (ref "R7") (pin "1") (pinfunction "1_1") (pintype "passive"))
      (node (ref "U6") (pin "5@1") (pinfunction "L3_5@1") (pintype "bidirectional"))
      (node (ref "U6") (pin "5@2") (pinfunction "L3_5@2") (pintype "bidirectional"))
      (node (ref "U6") (pin "6@1") (pinfunction "L2_6@1") (pintype "bidirectional"))
      (node (ref "U6") (pin "6@2") (pinfunction "L2_6@2") (pintype "bidirectional"))
    )
    (net (code "43") (name "Net-(F8-P$1-Pad1@1)") (class "Default")
      (node (ref "F8") (pin "1@1") (pinfunction "P$1_1@1") (pintype "bidirectional"))
      (node (ref "F8") (pin "1@2") (pinfunction "P$1_1@2") (pintype "bidirectional"))
      (node (ref "R8") (pin "1") (pinfunction "1_1") (pintype "passive"))
      (node (ref "U7") (pin "5@1") (pinfunction "L3_5@1") (pintype "bidirectional"))
      (node (ref "U7") (pin "5@2") (pinfunction "L3_5@2") (pintype "bidirectional"))
      (node (ref "U7") (pin "6@1") (pinfunction "L2_6@1") (pintype "bidirectional"))
      (node (ref "U7") (pin "6@2") (pinfunction "L2_6@2") (pintype "bidirectional"))
    )
    (net (code "44") (name "Net-(F9-P$1-Pad1@1)") (class "Default")
      (node (ref "F9") (pin "1@1") (pinfunction "P$1_1@1") (pintype "bidirectional"))
      (node (ref "F9") (pin "1@2") (pinfunction "P$1_1@2") (pintype "bidirectional"))
      (node (ref "R9") (pin "1") (pinfunction "1_1") (pintype "passive"))
      (node (ref "U8") (pin "5@1") (pinfunction "L3_5@1") (pintype "bidirectional"))
      (node (ref "U8") (pin "5@2") (pinfunction "L3_5@2") (pintype "bidirectional"))
      (node (ref "U8") (pin "6@1") (pinfunction "L2_6@1") (pintype "bidirectional"))
      (node (ref "U8") (pin "6@2") (pinfunction "L2_6@2") (pintype "bidirectional"))
    )
    (net (code "45") (name "Net-(F10-P$1-Pad1@1)") (class "Default")
      (node (ref "F10") (pin "1@1") (pinfunction "P$1_1@1") (pintype "bidirectional"))
      (node (ref "F10") (pin "1@2") (pinfunction "P$1_1@2") (pintype "bidirectional"))
      (node (ref "R10") (pin "1") (pinfunction "1_1") (pintype "passive"))
      (node (ref "U9") (pin "5@1") (pinfunction "L3_5@1") (pintype "bidirectional"))
      (node (ref "U9") (pin "5@2") (pinfunction "L3_5@2") (pintype "bidirectional"))
      (node (ref "U9") (pin "6@1") (pinfunction "L2_6@1") (pintype "bidirectional"))
      (node (ref "U9") (pin "6@2") (pinfunction "L2_6@2") (pintype "bidirectional"))
    )
    (net (code "46") (name "Net-(F11-P$1-Pad1@1)") (class "Default")
      (node (ref "F11") (pin "1@1") (pinfunction "P$1_1@1") (pintype "bidirectional"))
      (node (ref "F11") (pin "1@2") (pinfunction "P$1_1@2") (pintype "bidirectional"))
      (node (ref "R11") (pin "1") (pinfunction "1_1") (pintype "passive"))
      (node (ref "U10") (pin "5@1") (pinfunction "L3_5@1") (pintype "bidirectional"))
      (node (ref "U10") (pin "5@2") (pinfunction "L3_5@2") (pintype "bidirectional"))
      (node (ref "U10") (pin "6@1") (pinfunction "L2_6@1") (pintype "bidirectional"))
      (node (ref "U10") (pin "6@2") (pinfunction "L2_6@2") (pintype "bidirectional"))
    )
    (net (code "47") (name "Net-(F12-P$1-Pad1@1)") (class "Default")
      (node (ref "F12") (pin "1@1") (pinfunction "P$1_1@1") (pintype "bidirectional"))
      (node (ref "F12") (pin "1@2") (pinfunction "P$1_1@2") (pintype "bidirectional"))
      (node (ref "R12") (pin "1") (pinfunction "1_1") (pintype "passive"))
      (node (ref "U11") (pin "5@1") (pinfunction "L3_5@1") (pintype "bidirectional"))
      (node (ref "U11") (pin "5@2") (pinfunction "L3_5@2") (pintype "bidirectional"))
      (node (ref "U11") (pin "6@1") (pinfunction "L2_6@1") (pintype "bidirectional"))
      (node (ref "U11") (pin "6@2") (pinfunction "L2_6@2") (pintype "bidirectional"))
    )
    (net (code "48") (name "Net-(PS1-AC_L)") (class "Default")
      (node (ref "FL1") (pin "4") (pinfunction "4_4") (pintype "passive"))
      (node (ref "PS1") (pin "1") (pinfunction "AC_L_1") (pintype "passive"))
    )
    (net (code "49") (name "Net-(PS1-AC_N)") (class "Default")
      (node (ref "FL1") (pin "3") (pinfunction "3_3") (pintype "passive"))
      (node (ref "PS1") (pin "2") (pinfunction "AC_N_2") (pintype "passive"))
    )
    (net (code "50") (name "Net-(RN2A-2)") (class "Default")
      (node (ref "RN2") (pin "7") (pinfunction "2_7") (pintype "passive"))
      (node (ref "RN2") (pin "8") (pinfunction "2_8") (pintype "passive"))
    )
    (net (code "51") (name "Net-(RN2B-1)") (class "Default")
      (node (ref "RN2") (pin "2") (pinfunction "1_2") (pintype "passive"))
      (node (ref "RN2") (pin "3") (pinfunction "1_3") (pintype "passive"))
    )
    (net (code "52") (name "Net-(RN2D-1)") (class "Default")
      (node (ref "D2") (pin "A") (pinfunction "A_A") (pintype "passive"))
      (node (ref "RN2") (pin "4") (pinfunction "1_4") (pintype "passive"))
    )
    (net (code "53") (name "Net-(RN3A-2)") (class "Default")
      (node (ref "RN3") (pin "8") (pinfunction "2_8") (pintype "passive"))
      (node (ref "U2") (pin "2@1") (pinfunction "A_2@1") (pintype "bidirectional"))
      (node (ref "U2") (pin "2@2") (pinfunction "A_2@2") (pintype "bidirectional"))
    )
    (net (code "54") (name "Net-(RN3B-2)") (class "Default")
      (node (ref "RN3") (pin "7") (pinfunction "2_7") (pintype "passive"))
      (node (ref "U3") (pin "2@1") (pinfunction "A_2@1") (pintype "bidirectional"))
      (node (ref "U3") (pin "2@2") (pinfunction "A_2@2") (pintype "bidirectional"))
    )
    (net (code "55") (name "Net-(RN3C-2)") (class "Default")
      (node (ref "RN3") (pin "6") (pinfunction "2_6") (pintype "passive"))
      (node (ref "U4") (pin "2@1") (pinfunction "A_2@1") (pintype "bidirectional"))
      (node (ref "U4") (pin "2@2") (pinfunction "A_2@2") (pintype "bidirectional"))
    )
    (net (code "56") (name "Net-(RN3D-2)") (class "Default")
      (node (ref "RN3") (pin "5") (pinfunction "2_5") (pintype "passive"))
      (node (ref "U5") (pin "2@1") (pinfunction "A_2@1") (pintype "bidirectional"))
      (node (ref "U5") (pin "2@2") (pinfunction "A_2@2") (pintype "bidirectional"))
    )
    (net (code "57") (name "Net-(RN5A-2)") (class "Default")
      (node (ref "RN5") (pin "8") (pinfunction "2_8") (pintype "passive"))
      (node (ref "U6") (pin "2@1") (pinfunction "A_2@1") (pintype "bidirectional"))
      (node (ref "U6") (pin "2@2") (pinfunction "A_2@2") (pintype "bidirectional"))
    )
    (net (code "58") (name "Net-(RN5B-2)") (class "Default")
      (node (ref "RN5") (pin "7") (pinfunction "2_7") (pintype "passive"))
      (node (ref "U7") (pin "2@1") (pinfunction "A_2@1") (pintype "bidirectional"))
      (node (ref "U7") (pin "2@2") (pinfunction "A_2@2") (pintype "bidirectional"))
    )
    (net (code "59") (name "Net-(RN5C-2)") (class "Default")
      (node (ref "RN5") (pin "6") (pinfunction "2_6") (pintype "passive"))
      (node (ref "U8") (pin "2@1") (pinfunction "A_2@1") (pintype "bidirectional"))
      (node (ref "U8") (pin "2@2") (pinfunction "A_2@2") (pintype "bidirectional"))
    )
    (net (code "60") (name "Net-(RN5D-2)") (class "Default")
      (node (ref "RN5") (pin "5") (pinfunction "2_5") (pintype "passive"))
      (node (ref "U9") (pin "2@1") (pinfunction "A_2@1") (pintype "bidirectional"))
      (node (ref "U9") (pin "2@2") (pinfunction "A_2@2") (pintype "bidirectional"))
    )
    (net (code "61") (name "Net-(RN8A-2)") (class "Default")
      (node (ref "RN8") (pin "8") (pinfunction "2_8") (pintype "passive"))
      (node (ref "U10") (pin "2@1") (pinfunction "A_2@1") (pintype "bidirectional"))
      (node (ref "U10") (pin "2@2") (pinfunction "A_2@2") (pintype "bidirectional"))
    )
    (net (code "62") (name "Net-(RN8B-2)") (class "Default")
      (node (ref "RN8") (pin "7") (pinfunction "2_7") (pintype "passive"))
      (node (ref "U11") (pin "2@1") (pinfunction "A_2@1") (pintype "bidirectional"))
      (node (ref "U11") (pin "2@2") (pinfunction "A_2@2") (pintype "bidirectional"))
    )
    (net (code "63") (name "Net-(X1B-KL)") (class "Default")
      (node (ref "F3") (pin "2@1") (pinfunction "P$2_2@1") (pintype "bidirectional"))
      (node (ref "F3") (pin "2@2") (pinfunction "P$2_2@2") (pintype "bidirectional"))
      (node (ref "X1") (pin "2") (pinfunction "KL_2") (pintype "passive"))
    )
    (net (code "64") (name "Net-(X2A-KL)") (class "Default")
      (node (ref "F5") (pin "2@1") (pinfunction "P$2_2@1") (pintype "bidirectional"))
      (node (ref "F5") (pin "2@2") (pinfunction "P$2_2@2") (pintype "bidirectional"))
      (node (ref "X2") (pin "1") (pinfunction "KL_1") (pintype "passive"))
    )
    (net (code "65") (name "Net-(X2C-KL)") (class "Default")
      (node (ref "F4") (pin "2@1") (pinfunction "P$2_2@1") (pintype "bidirectional"))
      (node (ref "F4") (pin "2@2") (pinfunction "P$2_2@2") (pintype "bidirectional"))
      (node (ref "X2") (pin "3") (pinfunction "KL_3") (pintype "passive"))
    )
    (net (code "66") (name "Net-(X3B-KL)") (class "Default")
      (node (ref "F6") (pin "2@1") (pinfunction "P$2_2@1") (pintype "bidirectional"))
      (node (ref "F6") (pin "2@2") (pinfunction "P$2_2@2") (pintype "bidirectional"))
      (node (ref "X3") (pin "2") (pinfunction "KL_2") (pintype "passive"))
    )
    (net (code "67") (name "Net-(X4B-KL)") (class "Default")
      (node (ref "F7") (pin "2@1") (pinfunction "P$2_2@1") (pintype "bidirectional"))
      (node (ref "F7") (pin "2@2") (pinfunction "P$2_2@2") (pintype "bidirectional"))
      (node (ref "X4") (pin "2") (pinfunction "KL_2") (pintype "passive"))
    )
    (net (code "68") (name "Net-(X5A-KL)") (class "Default")
      (node (ref "F9") (pin "2@1") (pinfunction "P$2_2@1") (pintype "bidirectional"))
      (node (ref "F9") (pin "2@2") (pinfunction "P$2_2@2") (pintype "bidirectional"))
      (node (ref "X5") (pin "1") (pinfunction "KL_1") (pintype "passive"))
    )
    (net (code "69") (name "Net-(X5C-KL)") (class "Default")
      (node (ref "F8") (pin "2@1") (pinfunction "P$2_2@1") (pintype "bidirectional"))
      (node (ref "F8") (pin "2@2") (pinfunction "P$2_2@2") (pintype "bidirectional"))
      (node (ref "X5") (pin "3") (pinfunction "KL_3") (pintype "passive"))
    )
    (net (code "70") (name "Net-(X6B-KL)") (class "Default")
      (node (ref "F10") (pin "2@1") (pinfunction "P$2_2@1") (pintype "bidirectional"))
      (node (ref "F10") (pin "2@2") (pinfunction "P$2_2@2") (pintype "bidirectional"))
      (node (ref "X6") (pin "2") (pinfunction "KL_2") (pintype "passive"))
    )
    (net (code "71") (name "Net-(X7B-KL)") (class "Default")
      (node (ref "F11") (pin "2@1") (pinfunction "P$2_2@1") (pintype "bidirectional"))
      (node (ref "F11") (pin "2@2") (pinfunction "P$2_2@2") (pintype "bidirectional"))
      (node (ref "X7") (pin "2") (pinfunction "KL_2") (pintype "passive"))
    )
    (net (code "72") (name "Net-(X10B-KL)") (class "Default")
      (node (ref "F12") (pin "2@1") (pinfunction "P$2_2@1") (pintype "bidirectional"))
      (node (ref "F12") (pin "2@2") (pinfunction "P$2_2@2") (pintype "bidirectional"))
      (node (ref "X10") (pin "2") (pinfunction "KL_2") (pintype "passive"))
    )
    (net (code "73") (name "RXD") (class "Default")
      (node (ref "J1") (pin "2") (pinfunction "TXO_2") (pintype "passive"))
      (node (ref "J4") (pin "4") (pinfunction "4_4") (pintype "passive"))
      (node (ref "U1") (pin "34") (pinfunction "RXD0_34") (pintype "passive"))
    )
    (net (code "74") (name "SCL") (class "Default")
      (node (ref "J8") (pin "10") (pinfunction "10_10") (pintype "passive"))
      (node (ref "RN1") (pin "1") (pinfunction "1_1") (pintype "passive"))
      (node (ref "U1") (pin "36") (pinfunction "IO22_36") (pintype "passive"))
    )
    (net (code "75") (name "SDA") (class "Default")
      (node (ref "J8") (pin "9") (pinfunction "9_9") (pintype "passive"))
      (node (ref "RN1") (pin "2") (pinfunction "1_2") (pintype "passive"))
      (node (ref "U1") (pin "33") (pinfunction "IO21_33") (pintype "passive"))
    )
    (net (code "76") (name "TXD") (class "Default")
      (node (ref "J1") (pin "3") (pinfunction "RXI_3") (pintype "passive"))
      (node (ref "J4") (pin "3") (pinfunction "3_3") (pintype "passive"))
      (node (ref "U1") (pin "35") (pinfunction "TXD0_35") (pintype "passive"))
    )
    (net (code "77") (name "VX-F-LIVE") (class "Default")
      (node (ref "C10") (pin "1") (pinfunction "1_1") (pintype "passive"))
      (node (ref "C11") (pin "1") (pinfunction "1_1") (pintype "passive"))
      (node (ref "C12") (pin "1") (pinfunction "1_1") (pintype "passive"))
      (node (ref "C13") (pin "1") (pinfunction "1_1") (pintype "passive"))
      (node (ref "C14") (pin "1") (pinfunction "1_1") (pintype "passive"))
      (node (ref "C15") (pin "1") (pinfunction "1_1") (pintype "passive"))
      (node (ref "C6") (pin "1") (pinfunction "1_1") (pintype "passive"))
      (node (ref "C7") (pin "1") (pinfunction "1_1") (pintype "passive"))
      (node (ref "C8") (pin "1") (pinfunction "1_1") (pintype "passive"))
      (node (ref "C9") (pin "1") (pinfunction "1_1") (pintype "passive"))
      (node (ref "F1") (pin "2@1") (pinfunction "P$2_2@1") (pintype "bidirectional"))
      (node (ref "F1") (pin "2@2") (pinfunction "P$2_2@2") (pintype "bidirectional"))
      (node (ref "U10") (pin "8@1") (pinfunction "L1_8@1") (pintype "bidirectional"))
      (node (ref "U10") (pin "8@2") (pinfunction "L1_8@2") (pintype "bidirectional"))
      (node (ref "U11") (pin "8@1") (pinfunction "L1_8@1") (pintype "bidirectional"))
      (node (ref "U11") (pin "8@2") (pinfunction "L1_8@2") (pintype "bidirectional"))
      (node (ref "U2") (pin "8@1") (pinfunction "L1_8@1") (pintype "bidirectional"))
      (node (ref "U2") (pin "8@2") (pinfunction "L1_8@2") (pintype "bidirectional"))
      (node (ref "U3") (pin "8@1") (pinfunction "L1_8@1") (pintype "bidirectional"))
      (node (ref "U3") (pin "8@2") (pinfunction "L1_8@2") (pintype "bidirectional"))
      (node (ref "U4") (pin "8@1") (pinfunction "L1_8@1") (pintype "bidirectional"))
      (node (ref "U4") (pin "8@2") (pinfunction "L1_8@2") (pintype "bidirectional"))
      (node (ref "U5") (pin "8@1") (pinfunction "L1_8@1") (pintype "bidirectional"))
      (node (ref "U5") (pin "8@2") (pinfunction "L1_8@2") (pintype "bidirectional"))
      (node (ref "U6") (pin "8@1") (pinfunction "L1_8@1") (pintype "bidirectional"))
      (node (ref "U6") (pin "8@2") (pinfunction "L1_8@2") (pintype "bidirectional"))
      (node (ref "U7") (pin "8@1") (pinfunction "L1_8@1") (pintype "bidirectional"))
      (node (ref "U7") (pin "8@2") (pinfunction "L1_8@2") (pintype "bidirectional"))
      (node (ref "U8") (pin "8@1") (pinfunction "L1_8@1") (pintype "bidirectional"))
      (node (ref "U8") (pin "8@2") (pinfunction "L1_8@2") (pintype "bidirectional"))
      (node (ref "U9") (pin "8@1") (pinfunction "L1_8@1") (pintype "bidirectional"))
      (node (ref "U9") (pin "8@2") (pinfunction "L1_8@2") (pintype "bidirectional"))
    )
    (net (code "78") (name "VX-LIVE") (class "Default")
      (node (ref "F1") (pin "1@1") (pinfunction "P$1_1@1") (pintype "bidirectional"))
      (node (ref "F1") (pin "1@2") (pinfunction "P$1_1@2") (pintype "bidirectional"))
      (node (ref "JP2") (pin "1") (pinfunction "1_1") (pintype "passive"))
      (node (ref "X12") (pin "2") (pinfunction "KL_2") (pintype "passive"))
    )
    (net (code "79") (name "VX-NEUTRAL") (class "Default")
      (node (ref "JP1") (pin "1") (pinfunction "1_1") (pintype "passive"))
      (node (ref "X1") (pin "1") (pinfunction "KL_1") (pintype "passive"))
      (node (ref "X1") (pin "3") (pinfunction "KL_3") (pintype "passive"))
      (node (ref "X10") (pin "1") (pinfunction "KL_1") (pintype "passive"))
      (node (ref "X12") (pin "1") (pinfunction "KL_1") (pintype "passive"))
      (node (ref "X2") (pin "2") (pinfunction "KL_2") (pintype "passive"))
      (node (ref "X3") (pin "1") (pinfunction "KL_1") (pintype "passive"))
      (node (ref "X3") (pin "3") (pinfunction "KL_3") (pintype "passive"))
      (node (ref "X4") (pin "1") (pinfunction "KL_1") (pintype "passive"))
      (node (ref "X4") (pin "3") (pinfunction "KL_3") (pintype "passive"))
      (node (ref "X5") (pin "2") (pinfunction "KL_2") (pintype "passive"))
      (node (ref "X6") (pin "1") (pinfunction "KL_1") (pintype "passive"))
      (node (ref "X6") (pin "3") (pinfunction "KL_3") (pintype "passive"))
      (node (ref "X7") (pin "1") (pinfunction "KL_1") (pintype "passive"))
      (node (ref "X7") (pin "3") (pinfunction "KL_3") (pintype "passive"))
    )
    (net (code "80") (name "unconnected-(J1-CTS-Pad5)") (class "Default")
      (node (ref "J1") (pin "5") (pinfunction "CTS_5") (pintype "passive"))
    )
    (net (code "81") (name "unconnected-(J4-M-PadM@1)") (class "Default")
      (node (ref "J4") (pin "M@1") (pinfunction "M_M@1") (pintype "passive"))
    )
    (net (code "82") (name "unconnected-(J4-M-PadM@2)") (class "Default")
      (node (ref "J4") (pin "M@2") (pinfunction "M_M@2") (pintype "passive"))
    )
    (net (code "83") (name "unconnected-(J8-M-PadM@1)") (class "Default")
      (node (ref "J8") (pin "M@1") (pinfunction "M_M@1") (pintype "passive"))
    )
    (net (code "84") (name "unconnected-(J8-M-PadM@2)") (class "Default")
      (node (ref "J8") (pin "M@2") (pinfunction "M_M@2") (pintype "passive"))
    )
    (net (code "85") (name "unconnected-(TO_DAUGHTER_BOARD-M-PadM@1)") (class "Default")
      (node (ref "TO_DAUGHTER_BOARD") (pin "M@1") (pinfunction "M_M@1") (pintype "passive"))
    )
    (net (code "86") (name "unconnected-(TO_DAUGHTER_BOARD-M-PadM@2)") (class "Default")
      (node (ref "TO_DAUGHTER_BOARD") (pin "M@2") (pinfunction "M_M@2") (pintype "passive"))
    )
    (net (code "87") (name "unconnected-(U1-CLK-Pad20)") (class "Default")
      (node (ref "U1") (pin "20") (pinfunction "CLK_20") (pintype "passive"))
    )
    (net (code "88") (name "unconnected-(U1-CMD-Pad19)") (class "Default")
      (node (ref "U1") (pin "19") (pinfunction "CMD_19") (pintype "passive"))
    )
    (net (code "89") (name "unconnected-(U1-IO17-Pad28)") (class "Default")
      (node (ref "U1") (pin "28") (pinfunction "IO17_28") (pintype "passive"))
    )
    (net (code "90") (name "unconnected-(U1-NC-Pad32)") (class "Default")
      (node (ref "U1") (pin "32") (pinfunction "NC_32") (pintype "passive"))
    )
    (net (code "91") (name "unconnected-(U1-SD0-Pad21)") (class "Default")
      (node (ref "U1") (pin "21") (pinfunction "SD0_21") (pintype "passive"))
    )
    (net (code "92") (name "unconnected-(U1-SD1-Pad22)") (class "Default")
      (node (ref "U1") (pin "22") (pinfunction "SD1_22") (pintype "passive"))
    )
    (net (code "93") (name "unconnected-(U1-SD2-Pad17)") (class "Default")
      (node (ref "U1") (pin "17") (pinfunction "SD2_17") (pintype "passive"))
    )
    (net (code "94") (name "unconnected-(U1-SD3-Pad18)") (class "Default")
      (node (ref "U1") (pin "18") (pinfunction "SD3_18") (pintype "passive"))
    )
    (net (code "95") (name "unconnected-(U1-SENS_V_N-Pad5)") (class "Default")
      (node (ref "U1") (pin "5") (pinfunction "SENS_V_N_5") (pintype "passive"))
    )
    (net (code "96") (name "unconnected-(U1-SENS_V_P-Pad4)") (class "Default")
      (node (ref "U1") (pin "4") (pinfunction "SENS_V_P_4") (pintype "passive"))
    )
  )
)
